# power_adc_module.net
KiCad netlist of a schematic drawn in EAGLE
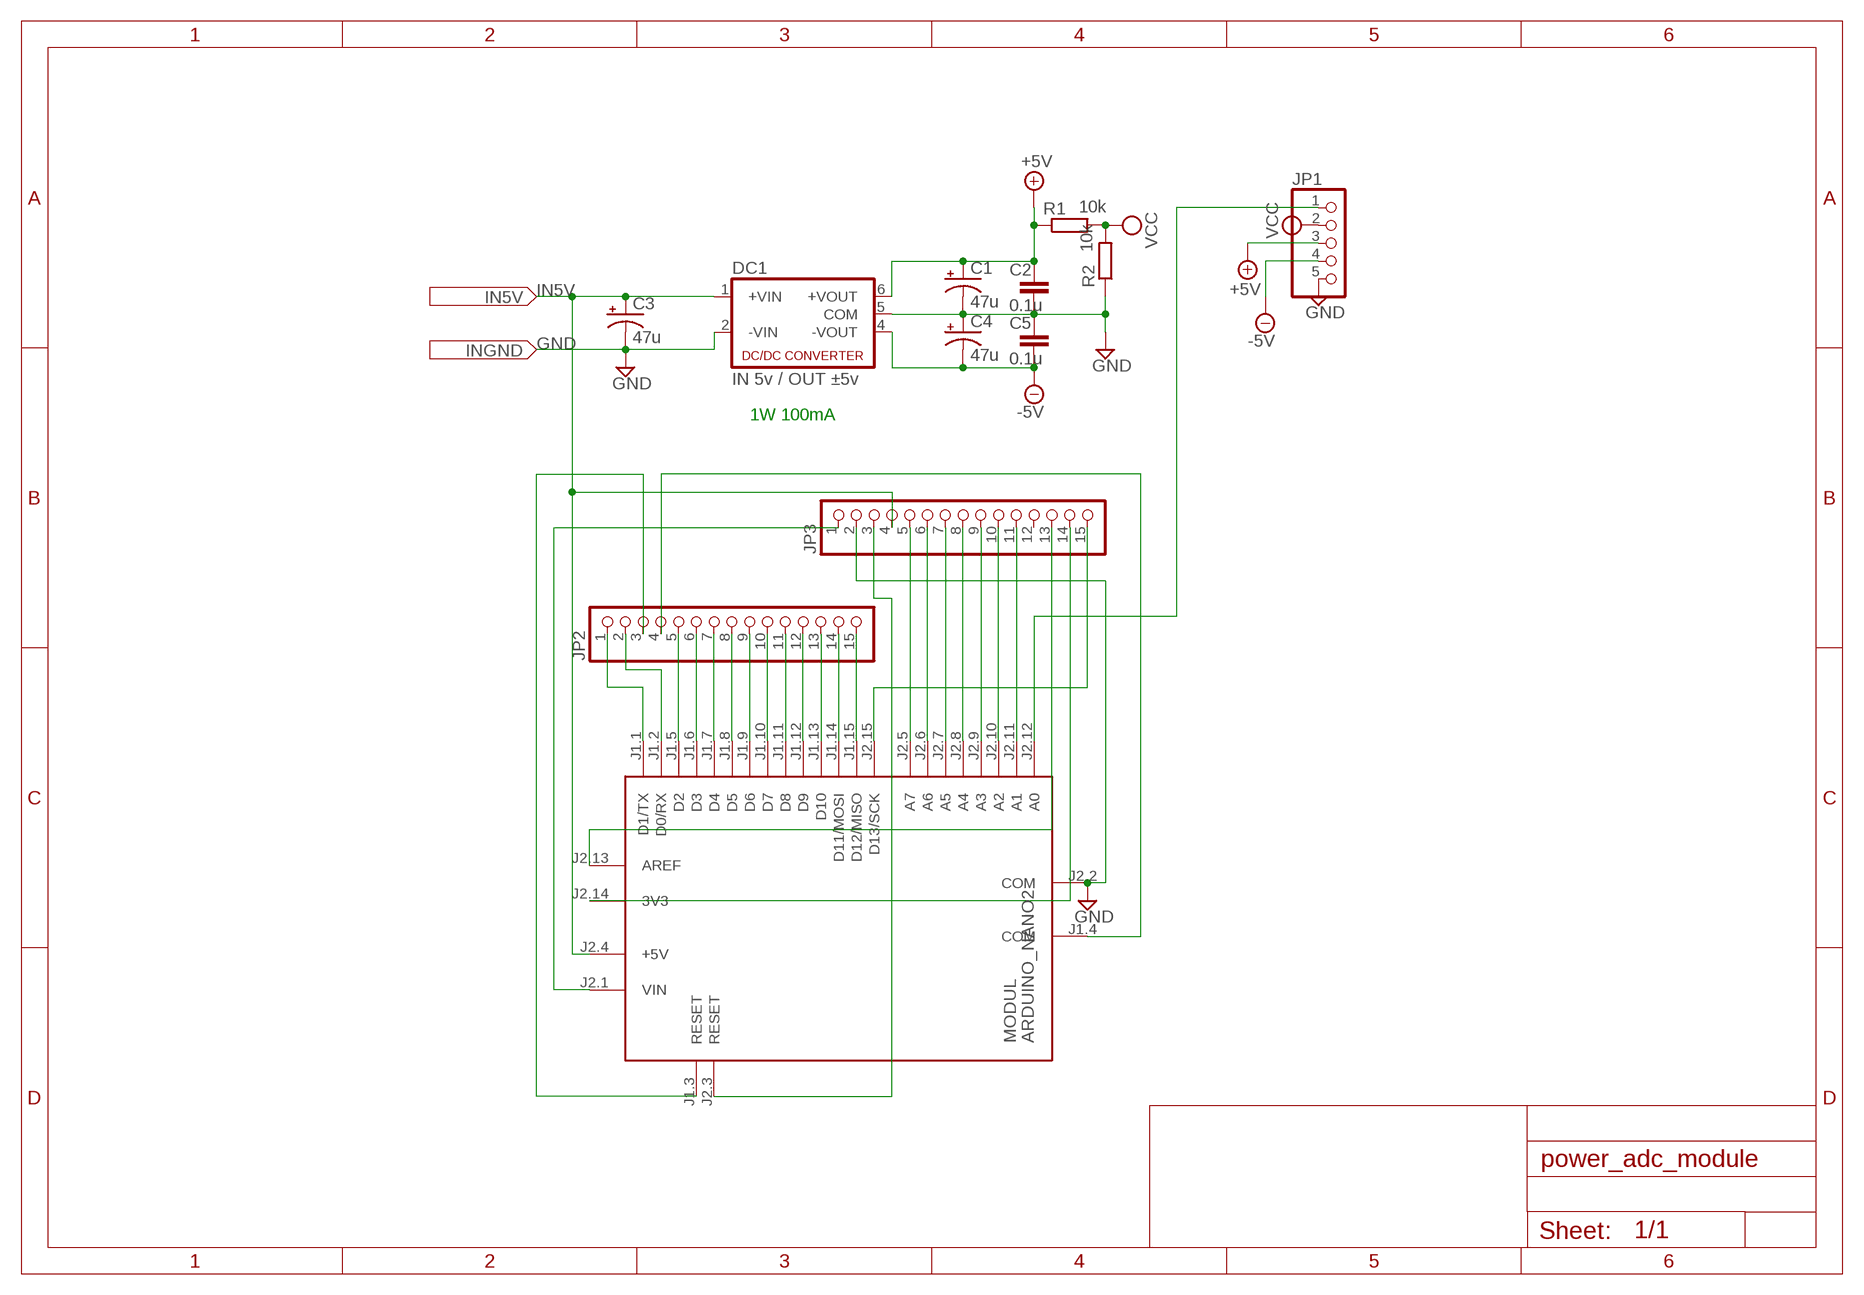
[diagram p0: schematic, sheet 1]

(export (version "E")
  (design (tool "Eeschema 10.0.6"))
  (components
    (comp (ref "C1")
      (value "47u")
      (footprint "eagle-import:E2,5-5")
      (libsource (lib "eagle-import") (part "CPOL-USE2.5-5"))
    )
    (comp (ref "C2")
      (value "0.1u")
      (footprint "eagle-import:C025-024X044")
      (libsource (lib "eagle-import") (part "C-EU025-024X044"))
    )
    (comp (ref "C3")
      (value "47u")
      (footprint "eagle-import:E2,5-5")
      (libsource (lib "eagle-import") (part "CPOL-USE2.5-5"))
    )
    (comp (ref "C4")
      (value "47u")
      (footprint "eagle-import:E2,5-5")
      (libsource (lib "eagle-import") (part "CPOL-USE2.5-5"))
    )
    (comp (ref "C5")
      (value "0.1u")
      (footprint "eagle-import:C025-024X044")
      (libsource (lib "eagle-import") (part "C-EU025-024X044"))
    )
    (comp (ref "DC1")
      (value "IN 5v / OUT ±5v")
      (footprint "eagle-import:NMA")
      (fields (field (name "MF") "C & D TECHNOLOGIES, INC") (field (name "MPN") "NMA0515SC"))
      (libsource (lib "eagle-import") (part "NMA"))
    )
    (comp (ref "JP1")
      (value "PINHD-1X5")
      (footprint "eagle-import:1X05")
      (libsource (lib "eagle-import") (part "PINHD-1X5"))
    )
    (comp (ref "JP2")
      (value "PINHD-1X15")
      (footprint "eagle-import:1X15")
      (libsource (lib "eagle-import") (part "PINHD-1X15"))
    )
    (comp (ref "JP3")
      (value "PINHD-1X15")
      (footprint "eagle-import:1X15")
      (libsource (lib "eagle-import") (part "PINHD-1X15"))
    )
    (comp (ref "MODUL")
      (value "ARDUINO_NANO2")
      (footprint "eagle-import:ARDUINO_NANO2")
      (libsource (lib "eagle-import") (part "ARDUINO_NANO2"))
    )
    (comp (ref "R1")
      (value "10k")
      (footprint "eagle-import:0204_7")
      (libsource (lib "eagle-import") (part "R-EU_0204/7"))
    )
    (comp (ref "R2")
      (value "10k")
      (footprint "eagle-import:0204_7")
      (libsource (lib "eagle-import") (part "R-EU_0204/7"))
    )
  )
  (nets
    (net (code "1") (name "+5V") (class "Default")
      (node (ref "C1") (pin "+") (pinfunction "+_+") (pintype "passive"))
      (node (ref "C2") (pin "1") (pinfunction "1_1") (pintype "passive"))
      (node (ref "DC1") (pin "6") (pinfunction "+VOUT_6") (pintype "passive"))
      (node (ref "JP1") (pin "3") (pinfunction "3_3") (pintype "passive"))
      (node (ref "R1") (pin "1") (pinfunction "1_1") (pintype "passive"))
    )
    (net (code "2") (name "-5V") (class "Default")
      (node (ref "C4") (pin "-") (pinfunction "-_-") (pintype "passive"))
      (node (ref "C5") (pin "2") (pinfunction "2_2") (pintype "passive"))
      (node (ref "DC1") (pin "4") (pinfunction "-VOUT_4") (pintype "passive"))
      (node (ref "JP1") (pin "4") (pinfunction "4_4") (pintype "passive"))
    )
    (net (code "3") (name "/IN5V") (class "Default")
      (node (ref "C3") (pin "+") (pinfunction "+_+") (pintype "passive"))
      (node (ref "DC1") (pin "1") (pinfunction "+VIN_1") (pintype "passive"))
      (node (ref "JP3") (pin "4") (pinfunction "4_4") (pintype "passive"))
      (node (ref "MODUL") (pin "J2.4") (pinfunction "+5V_J2.4") (pintype "power_in"))
    )
    (net (code "4") (name "GND") (class "Default")
      (node (ref "C1") (pin "-") (pinfunction "-_-") (pintype "passive"))
      (node (ref "C2") (pin "2") (pinfunction "2_2") (pintype "passive"))
      (node (ref "C3") (pin "-") (pinfunction "-_-") (pintype "passive"))
      (node (ref "C4") (pin "+") (pinfunction "+_+") (pintype "passive"))
      (node (ref "C5") (pin "1") (pinfunction "1_1") (pintype "passive"))
      (node (ref "DC1") (pin "2") (pinfunction "-VIN_2") (pintype "passive"))
      (node (ref "DC1") (pin "5") (pinfunction "COM_5") (pintype "passive"))
      (node (ref "JP1") (pin "5") (pinfunction "5_5") (pintype "passive"))
      (node (ref "JP3") (pin "2") (pinfunction "2_2") (pintype "passive"))
      (node (ref "MODUL") (pin "J2.2") (pinfunction "COM_J2.2") (pintype "power_in"))
      (node (ref "R2") (pin "1") (pinfunction "1_1") (pintype "passive"))
    )
    (net (code "5") (name "Net-(JP2-Pad3)") (class "Default")
      (node (ref "JP2") (pin "3") (pinfunction "3_3") (pintype "passive"))
      (node (ref "MODUL") (pin "J1.3") (pinfunction "RESET_J1.3") (pintype "bidirectional"))
    )
    (net (code "6") (name "Net-(JP2-Pad4)") (class "Default")
      (node (ref "JP2") (pin "4") (pinfunction "4_4") (pintype "passive"))
      (node (ref "MODUL") (pin "J1.4") (pinfunction "COM_J1.4") (pintype "power_in"))
    )
    (net (code "7") (name "Net-(JP3-Pad3)") (class "Default")
      (node (ref "JP3") (pin "3") (pinfunction "3_3") (pintype "passive"))
      (node (ref "MODUL") (pin "J2.3") (pinfunction "RESET_J2.3") (pintype "bidirectional"))
    )
    (net (code "8") (name "Net-(MODUL-3V3)") (class "Default")
      (node (ref "JP3") (pin "14") (pinfunction "14_14") (pintype "passive"))
      (node (ref "MODUL") (pin "J2.14") (pinfunction "3V3_J2.14") (pintype "power_in"))
    )
    (net (code "9") (name "Net-(MODUL-A0)") (class "Default")
      (node (ref "JP1") (pin "1") (pinfunction "1_1") (pintype "passive"))
      (node (ref "MODUL") (pin "J2.12") (pinfunction "A0_J2.12") (pintype "bidirectional"))
    )
    (net (code "10") (name "Net-(MODUL-A1)") (class "Default")
      (node (ref "JP3") (pin "11") (pinfunction "11_11") (pintype "passive"))
      (node (ref "MODUL") (pin "J2.11") (pinfunction "A1_J2.11") (pintype "bidirectional"))
    )
    (net (code "11") (name "Net-(MODUL-A2)") (class "Default")
      (node (ref "JP3") (pin "10") (pinfunction "10_10") (pintype "passive"))
      (node (ref "MODUL") (pin "J2.10") (pinfunction "A2_J2.10") (pintype "bidirectional"))
    )
    (net (code "12") (name "Net-(MODUL-A3)") (class "Default")
      (node (ref "JP3") (pin "9") (pinfunction "9_9") (pintype "passive"))
      (node (ref "MODUL") (pin "J2.9") (pinfunction "A3_J2.9") (pintype "bidirectional"))
    )
    (net (code "13") (name "Net-(MODUL-A4)") (class "Default")
      (node (ref "JP3") (pin "8") (pinfunction "8_8") (pintype "passive"))
      (node (ref "MODUL") (pin "J2.8") (pinfunction "A4_J2.8") (pintype "bidirectional"))
    )
    (net (code "14") (name "Net-(MODUL-A5)") (class "Default")
      (node (ref "JP3") (pin "7") (pinfunction "7_7") (pintype "passive"))
      (node (ref "MODUL") (pin "J2.7") (pinfunction "A5_J2.7") (pintype "bidirectional"))
    )
    (net (code "15") (name "Net-(MODUL-A6)") (class "Default")
      (node (ref "JP3") (pin "6") (pinfunction "6_6") (pintype "passive"))
      (node (ref "MODUL") (pin "J2.6") (pinfunction "A6_J2.6") (pintype "bidirectional"))
    )
    (net (code "16") (name "Net-(MODUL-A7)") (class "Default")
      (node (ref "JP3") (pin "5") (pinfunction "5_5") (pintype "passive"))
      (node (ref "MODUL") (pin "J2.5") (pinfunction "A7_J2.5") (pintype "bidirectional"))
    )
    (net (code "17") (name "Net-(MODUL-AREF)") (class "Default")
      (node (ref "JP3") (pin "13") (pinfunction "13_13") (pintype "passive"))
      (node (ref "MODUL") (pin "J2.13") (pinfunction "AREF_J2.13") (pintype "power_in"))
    )
    (net (code "18") (name "Net-(MODUL-D0{slash}RX)") (class "Default")
      (node (ref "JP2") (pin "2") (pinfunction "2_2") (pintype "passive"))
      (node (ref "MODUL") (pin "J1.2") (pinfunction "D0/RX_J1.2") (pintype "bidirectional"))
    )
    (net (code "19") (name "Net-(MODUL-D1{slash}TX)") (class "Default")
      (node (ref "JP2") (pin "1") (pinfunction "1_1") (pintype "passive"))
      (node (ref "MODUL") (pin "J1.1") (pinfunction "D1/TX_J1.1") (pintype "bidirectional"))
    )
    (net (code "20") (name "Net-(MODUL-D2)") (class "Default")
      (node (ref "JP2") (pin "5") (pinfunction "5_5") (pintype "passive"))
      (node (ref "MODUL") (pin "J1.5") (pinfunction "D2_J1.5") (pintype "bidirectional"))
    )
    (net (code "21") (name "Net-(MODUL-D3)") (class "Default")
      (node (ref "JP2") (pin "6") (pinfunction "6_6") (pintype "passive"))
      (node (ref "MODUL") (pin "J1.6") (pinfunction "D3_J1.6") (pintype "bidirectional"))
    )
    (net (code "22") (name "Net-(MODUL-D4)") (class "Default")
      (node (ref "JP2") (pin "7") (pinfunction "7_7") (pintype "passive"))
      (node (ref "MODUL") (pin "J1.7") (pinfunction "D4_J1.7") (pintype "bidirectional"))
    )
    (net (code "23") (name "Net-(MODUL-D5)") (class "Default")
      (node (ref "JP2") (pin "8") (pinfunction "8_8") (pintype "passive"))
      (node (ref "MODUL") (pin "J1.8") (pinfunction "D5_J1.8") (pintype "bidirectional"))
    )
    (net (code "24") (name "Net-(MODUL-D6)") (class "Default")
      (node (ref "JP2") (pin "9") (pinfunction "9_9") (pintype "passive"))
      (node (ref "MODUL") (pin "J1.9") (pinfunction "D6_J1.9") (pintype "bidirectional"))
    )
    (net (code "25") (name "Net-(MODUL-D7)") (class "Default")
      (node (ref "JP2") (pin "10") (pinfunction "10_10") (pintype "passive"))
      (node (ref "MODUL") (pin "J1.10") (pinfunction "D7_J1.10") (pintype "bidirectional"))
    )
    (net (code "26") (name "Net-(MODUL-D8)") (class "Default")
      (node (ref "JP2") (pin "11") (pinfunction "11_11") (pintype "passive"))
      (node (ref "MODUL") (pin "J1.11") (pinfunction "D8_J1.11") (pintype "bidirectional"))
    )
    (net (code "27") (name "Net-(MODUL-D9)") (class "Default")
      (node (ref "JP2") (pin "12") (pinfunction "12_12") (pintype "passive"))
      (node (ref "MODUL") (pin "J1.12") (pinfunction "D9_J1.12") (pintype "bidirectional"))
    )
    (net (code "28") (name "Net-(MODUL-D10)") (class "Default")
      (node (ref "JP2") (pin "13") (pinfunction "13_13") (pintype "passive"))
      (node (ref "MODUL") (pin "J1.13") (pinfunction "D10_J1.13") (pintype "bidirectional"))
    )
    (net (code "29") (name "Net-(MODUL-D11{slash}MOSI)") (class "Default")
      (node (ref "JP2") (pin "14") (pinfunction "14_14") (pintype "passive"))
      (node (ref "MODUL") (pin "J1.14") (pinfunction "D11/MOSI_J1.14") (pintype "bidirectional"))
    )
    (net (code "30") (name "Net-(MODUL-D12{slash}MISO)") (class "Default")
      (node (ref "JP2") (pin "15") (pinfunction "15_15") (pintype "passive"))
      (node (ref "MODUL") (pin "J1.15") (pinfunction "D12/MISO_J1.15") (pintype "bidirectional"))
    )
    (net (code "31") (name "Net-(MODUL-D13{slash}SCK)") (class "Default")
      (node (ref "JP3") (pin "15") (pinfunction "15_15") (pintype "passive"))
      (node (ref "MODUL") (pin "J2.15") (pinfunction "D13/SCK_J2.15") (pintype "bidirectional"))
    )
    (net (code "32") (name "Net-(MODUL-VIN)") (class "Default")
      (node (ref "JP3") (pin "1") (pinfunction "1_1") (pintype "passive"))
      (node (ref "MODUL") (pin "J2.1") (pinfunction "VIN_J2.1") (pintype "power_in"))
    )
    (net (code "33") (name "VCC") (class "Default")
      (node (ref "JP1") (pin "2") (pinfunction "2_2") (pintype "passive"))
      (node (ref "R1") (pin "2") (pinfunction "2_2") (pintype "passive"))
      (node (ref "R2") (pin "2") (pinfunction "2_2") (pintype "passive"))
    )
    (net (code "34") (name "unconnected-(JP3-Pad12)") (class "Default")
      (node (ref "JP3") (pin "12") (pinfunction "12_12") (pintype "passive"))
    )
  )
)
